# masterboard_b13.net
KiCad netlist of a schematic drawn in EAGLE
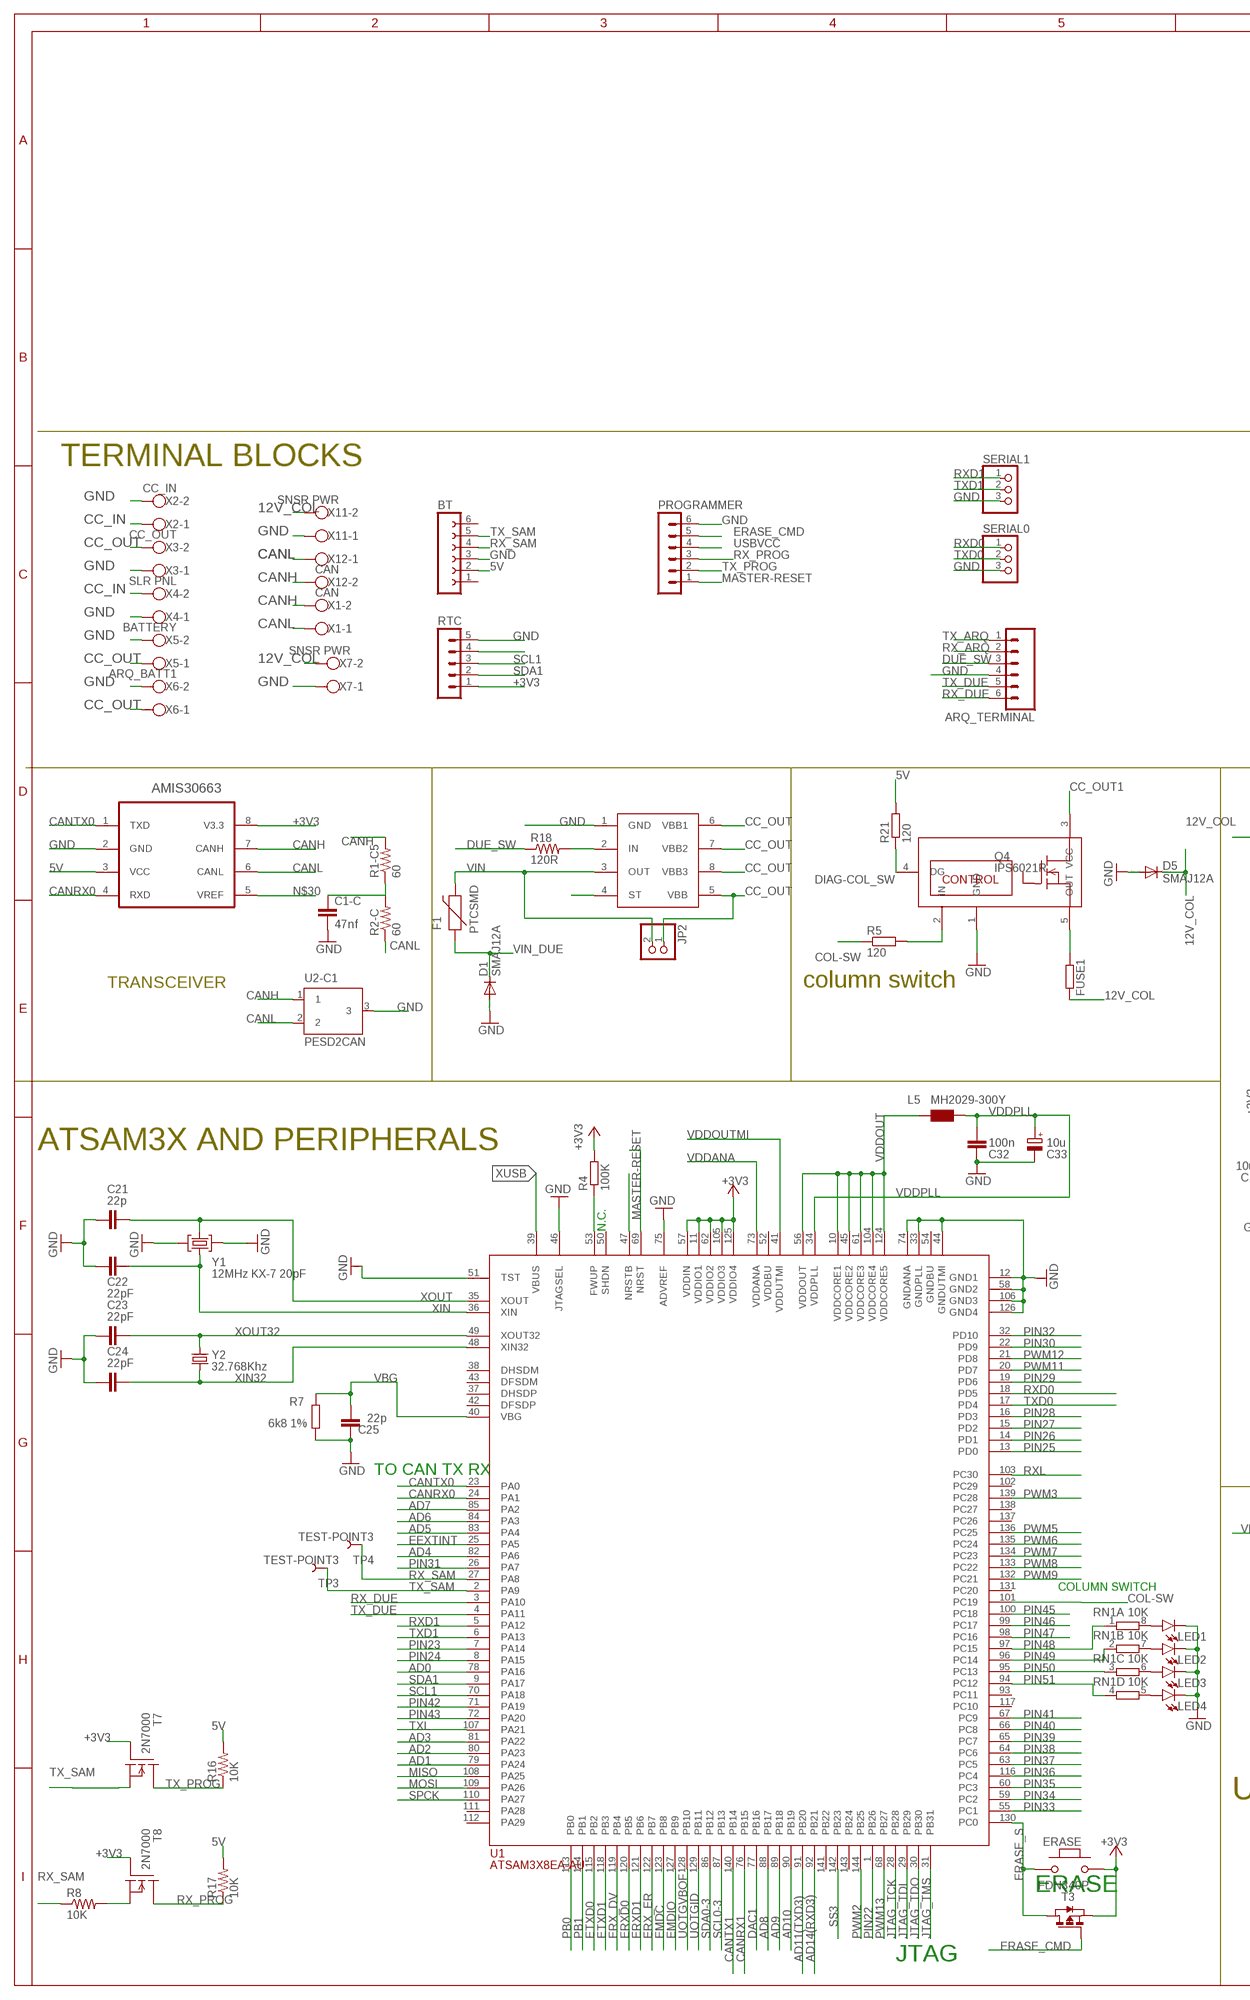
[diagram p0: schematic, sheet 1, part 1 of 2]
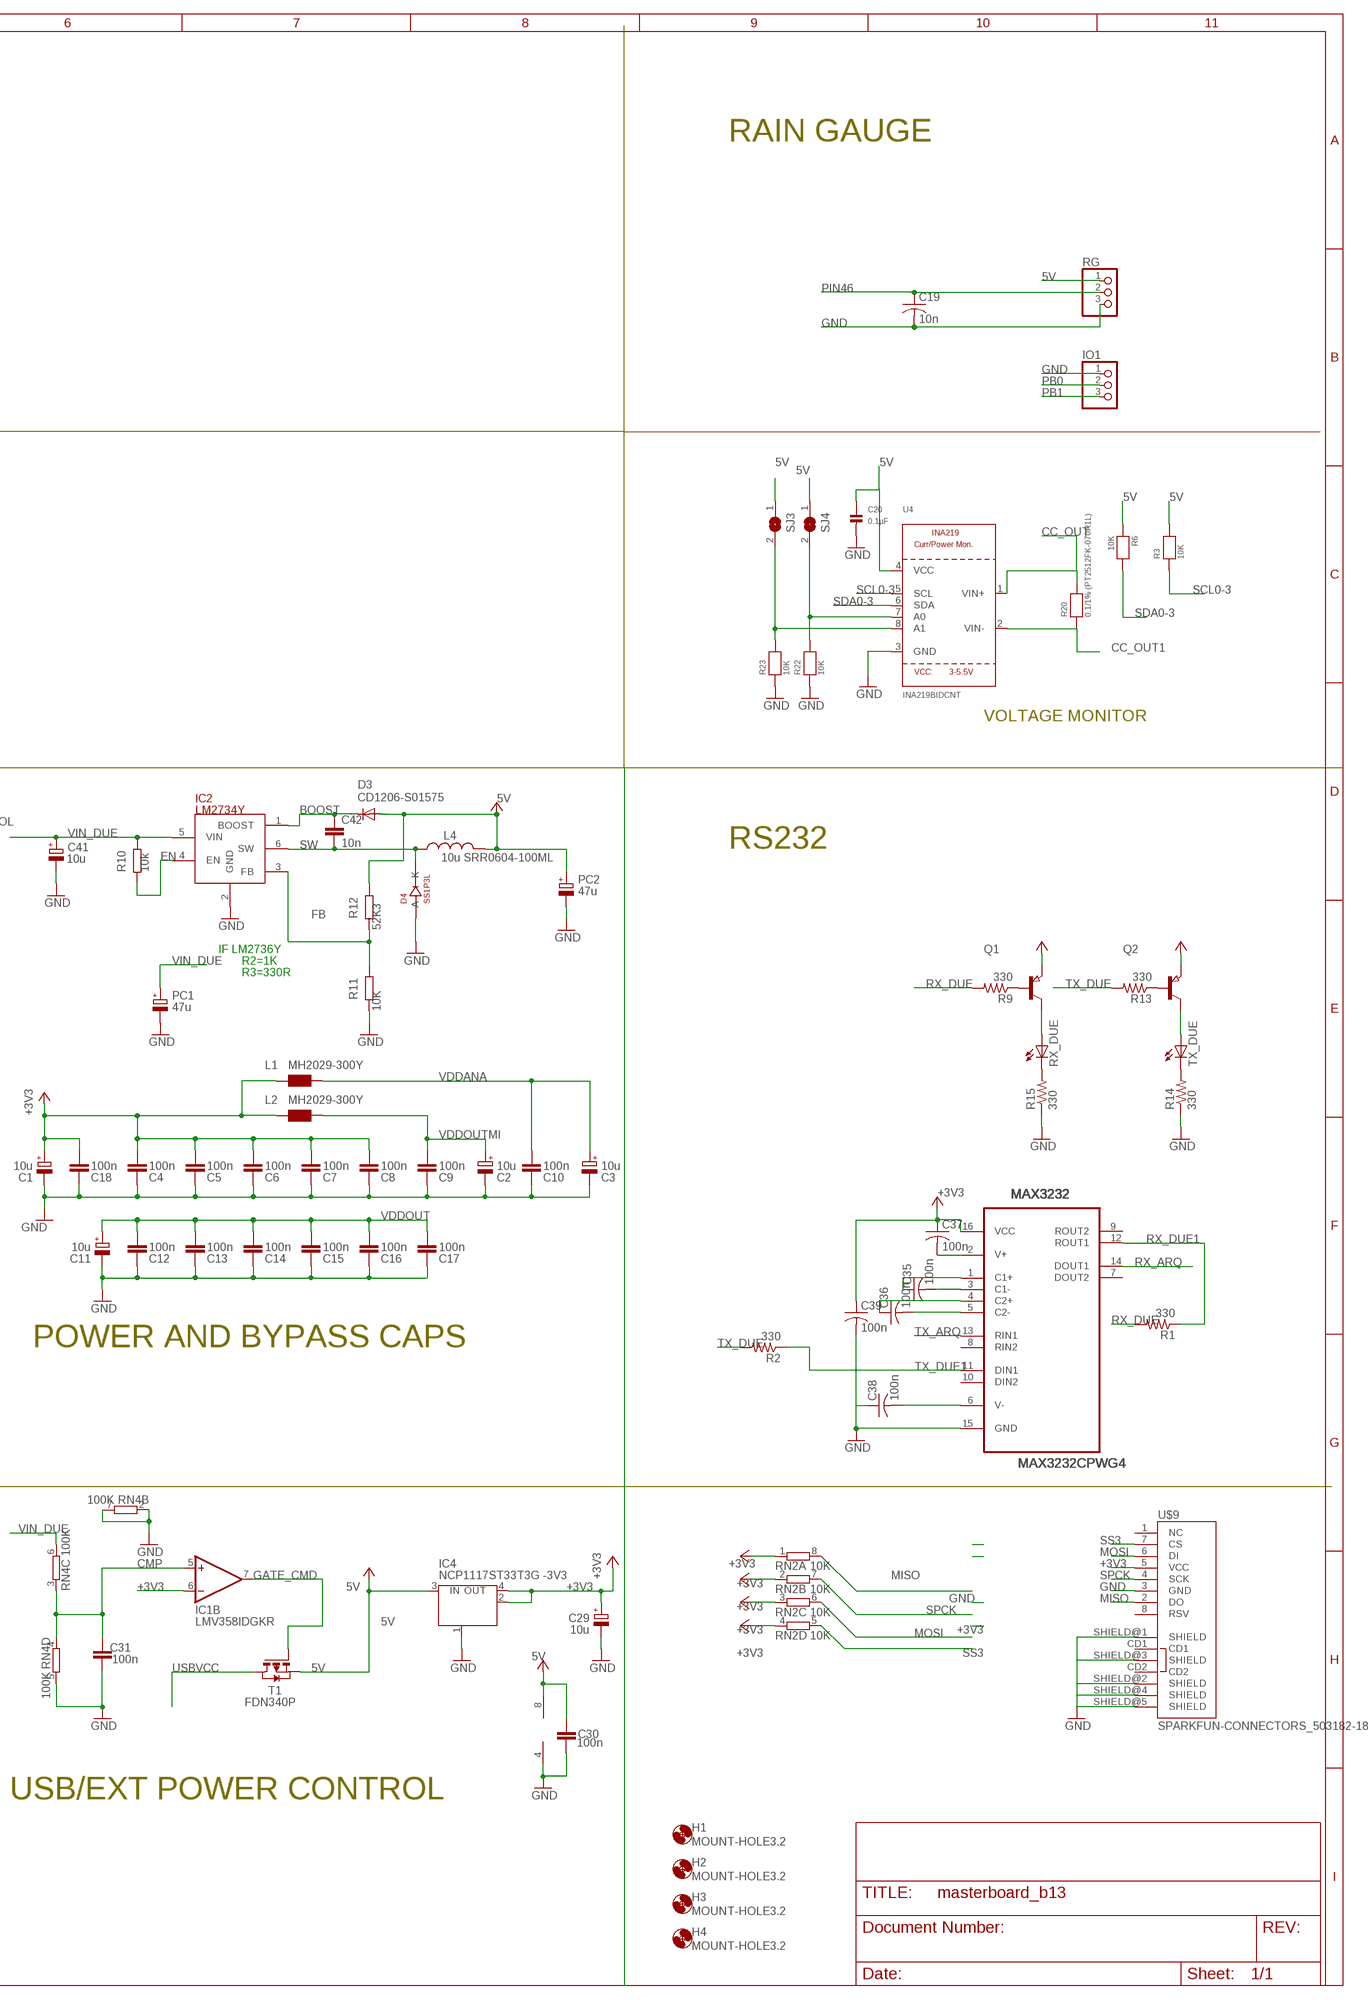
[diagram p1: schematic, sheet 1, part 2 of 2]

(export (version "E")
  (design (tool "Eeschema 10.0.6"))
  (components
    (comp (ref "ARQ_TERMINAL")
      (value "M06POLAR")
      (footprint "eagle-import:MOLEX-1X6")
      (libsource (lib "eagle-import") (part "M06POLAR"))
    )
    (comp (ref "BT")
      (value "FE06-1")
      (footprint "eagle-import:FE06")
      (libsource (lib "eagle-import") (part "FE06-1"))
    )
    (comp (ref "C1")
      (value "10u")
      (footprint "eagle-import:SMC_B")
      (libsource (lib "eagle-import") (part "CPOL-EUSMCB"))
    )
    (comp (ref "C1-C")
      (value "47nf")
      (footprint "eagle-import:C0805")
      (libsource (lib "eagle-import") (part "rcl_334_C-EUC0805"))
    )
    (comp (ref "C2")
      (value "10u")
      (footprint "eagle-import:SMC_B")
      (libsource (lib "eagle-import") (part "CPOL-EUSMCB"))
    )
    (comp (ref "C3")
      (value "10u")
      (footprint "eagle-import:SMC_B")
      (libsource (lib "eagle-import") (part "CPOL-EUSMCB"))
    )
    (comp (ref "C4")
      (value "100n")
      (footprint "eagle-import:C0402")
      (libsource (lib "eagle-import") (part "C-EUC0402"))
    )
    (comp (ref "C5")
      (value "100n")
      (footprint "eagle-import:C0402")
      (libsource (lib "eagle-import") (part "C-EUC0402"))
    )
    (comp (ref "C6")
      (value "100n")
      (footprint "eagle-import:C0402")
      (libsource (lib "eagle-import") (part "C-EUC0402"))
    )
    (comp (ref "C7")
      (value "100n")
      (footprint "eagle-import:C0402")
      (libsource (lib "eagle-import") (part "C-EUC0402"))
    )
    (comp (ref "C8")
      (value "100n")
      (footprint "eagle-import:C0402")
      (libsource (lib "eagle-import") (part "C-EUC0402"))
    )
    (comp (ref "C9")
      (value "100n")
      (footprint "eagle-import:C0402")
      (libsource (lib "eagle-import") (part "C-EUC0402"))
    )
    (comp (ref "C10")
      (value "100n")
      (footprint "eagle-import:C0402")
      (libsource (lib "eagle-import") (part "C-EUC0402"))
    )
    (comp (ref "C11")
      (value "10u")
      (footprint "eagle-import:SMC_B")
      (libsource (lib "eagle-import") (part "CPOL-EUSMCB"))
    )
    (comp (ref "C12")
      (value "100n")
      (footprint "eagle-import:C0402")
      (libsource (lib "eagle-import") (part "C-EUC0402"))
    )
    (comp (ref "C13")
      (value "100n")
      (footprint "eagle-import:C0402")
      (libsource (lib "eagle-import") (part "C-EUC0402"))
    )
    (comp (ref "C14")
      (value "100n")
      (footprint "eagle-import:C0402")
      (libsource (lib "eagle-import") (part "C-EUC0402"))
    )
    (comp (ref "C15")
      (value "100n")
      (footprint "eagle-import:C0402")
      (libsource (lib "eagle-import") (part "C-EUC0402"))
    )
    (comp (ref "C16")
      (value "100n")
      (footprint "eagle-import:C0402")
      (libsource (lib "eagle-import") (part "C-EUC0402"))
    )
    (comp (ref "C17")
      (value "100n")
      (footprint "eagle-import:C0402")
      (libsource (lib "eagle-import") (part "C-EUC0402"))
    )
    (comp (ref "C18")
      (value "100n")
      (footprint "eagle-import:C0402")
      (libsource (lib "eagle-import") (part "C-EUC0402"))
    )
    (comp (ref "C19")
      (value "10n")
      (footprint "eagle-import:C0603")
      (libsource (lib "eagle-import") (part "C-USC0603"))
    )
    (comp (ref "C20")
      (value "0.1µF")
      (footprint "eagle-import:0603-MINI")
      (fields (field (name "MPN") "04023C104KAT2A"))
      (libsource (lib "eagle-import") (part "CAP_CERAMIC0603MINI"))
    )
    (comp (ref "C21")
      (value "22p")
      (footprint "eagle-import:C0402")
      (libsource (lib "eagle-import") (part "C-EUC0402"))
    )
    (comp (ref "C22")
      (value "22pF")
      (footprint "eagle-import:C0402")
      (libsource (lib "eagle-import") (part "C-EUC0402"))
    )
    (comp (ref "C23")
      (value "22pF")
      (footprint "eagle-import:C0402")
      (libsource (lib "eagle-import") (part "C-EUC0402"))
    )
    (comp (ref "C24")
      (value "22pF")
      (footprint "eagle-import:C0402")
      (libsource (lib "eagle-import") (part "C-EUC0402"))
    )
    (comp (ref "C25")
      (value "22p")
      (footprint "eagle-import:C0402")
      (libsource (lib "eagle-import") (part "C-EUC0402"))
    )
    (comp (ref "C29")
      (value "10u")
      (footprint "eagle-import:SMC_B")
      (libsource (lib "eagle-import") (part "CPOL-EUSMCB"))
    )
    (comp (ref "C30")
      (value "100n")
      (footprint "eagle-import:C0402")
      (libsource (lib "eagle-import") (part "C-EUC0402"))
    )
    (comp (ref "C31")
      (value "100n")
      (footprint "eagle-import:C0402")
      (libsource (lib "eagle-import") (part "C-EUC0402"))
    )
    (comp (ref "C32")
      (value "100n")
      (footprint "eagle-import:C0402")
      (libsource (lib "eagle-import") (part "C-EUC0402"))
    )
    (comp (ref "C33")
      (value "10u")
      (footprint "eagle-import:SMC_B")
      (libsource (lib "eagle-import") (part "CPOL-EUSMCB"))
    )
    (comp (ref "C35")
      (value "100n")
      (footprint "eagle-import:C0603")
      (libsource (lib "eagle-import") (part "C-USC0603"))
    )
    (comp (ref "C36")
      (value "100n")
      (footprint "eagle-import:C0603")
      (libsource (lib "eagle-import") (part "C-USC0603"))
    )
    (comp (ref "C37")
      (value "100n")
      (footprint "eagle-import:C0603")
      (libsource (lib "eagle-import") (part "C-USC0603"))
    )
    (comp (ref "C38")
      (value "100n")
      (footprint "eagle-import:C0603")
      (libsource (lib "eagle-import") (part "C-USC0603"))
    )
    (comp (ref "C39")
      (value "100n")
      (footprint "eagle-import:C0603")
      (libsource (lib "eagle-import") (part "C-USC0603"))
    )
    (comp (ref "C41")
      (value "10u")
      (footprint "eagle-import:SMC_B")
      (libsource (lib "eagle-import") (part "CPOL-EUSMCB"))
    )
    (comp (ref "C42")
      (value "10n")
      (footprint "eagle-import:C0603-ROUND")
      (libsource (lib "eagle-import") (part "C-EUC0603"))
    )
    (comp (ref "D1")
      (value "SMAJ12A")
      (footprint "eagle-import:DO214AC")
      (libsource (lib "eagle-import") (part "DIODE-DO214AC"))
    )
    (comp (ref "D3")
      (value "CD1206-S01575")
      (footprint "eagle-import:MINIMELF")
      (libsource (lib "eagle-import") (part "DIODE-MINIMELF"))
    )
    (comp (ref "D4")
      (value "SS1P3L")
      (footprint "eagle-import:DO220AAL")
      (libsource (lib "eagle-import") (part "SS1P3L"))
    )
    (comp (ref "D5")
      (value "SMAJ12A")
      (footprint "eagle-import:DO214AC")
      (libsource (lib "eagle-import") (part "DIODE-DO214AC"))
    )
    (comp (ref "ERASE")
      (value "MYSMD_PB157")
      (footprint "eagle-import:SMD_157SW")
      (libsource (lib "eagle-import") (part "MYSMD_PB157"))
    )
    (comp (ref "F1")
      (value "PTCSMD")
      (footprint "eagle-import:PTC-1206")
      (libsource (lib "eagle-import") (part "PTCSMD"))
    )
    (comp (ref "FUSE1")
      (value "R-EU_1812X7R")
      (footprint "eagle-import:1812X7R")
      (libsource (lib "eagle-import") (part "R-EU_1812X7R"))
    )
    (comp (ref "H1")
      (value "MOUNT-HOLE3.2")
      (footprint "eagle-import:3,2")
      (libsource (lib "eagle-import") (part "MOUNT-HOLE3.2"))
    )
    (comp (ref "H2")
      (value "MOUNT-HOLE3.2")
      (footprint "eagle-import:3,2")
      (libsource (lib "eagle-import") (part "MOUNT-HOLE3.2"))
    )
    (comp (ref "H3")
      (value "MOUNT-HOLE3.2")
      (footprint "eagle-import:3,2")
      (libsource (lib "eagle-import") (part "MOUNT-HOLE3.2"))
    )
    (comp (ref "H4")
      (value "MOUNT-HOLE3.2")
      (footprint "eagle-import:3,2")
      (libsource (lib "eagle-import") (part "MOUNT-HOLE3.2"))
    )
    (comp (ref "IC1")
      (value "LMV358IDGKR")
      (footprint "eagle-import:MSOP08")
      (libsource (lib "eagle-import") (part "LMV358?MMX"))
    )
    (comp (ref "IC2")
      (value "LM2734Y")
      (footprint "eagle-import:SOT23-6")
      (libsource (lib "eagle-import") (part "LM2736Y"))
    )
    (comp (ref "IC4")
      (value "NCP1117ST33T3G -3V3")
      (footprint "eagle-import:SOT223")
      (libsource (lib "eagle-import") (part "MC33269ST-3.3T3"))
    )
    (comp (ref "IO1")
      (value "PINHD-1X3")
      (footprint "eagle-import:1X03")
      (libsource (lib "eagle-import") (part "PINHD-1X3"))
    )
    (comp (ref "JP2")
      (value "PINHD-1X2")
      (footprint "eagle-import:1X02")
      (libsource (lib "eagle-import") (part "PINHD-1X2"))
    )
    (comp (ref "L1")
      (value "MH2029-300Y")
      (footprint "eagle-import:0805")
      (libsource (lib "eagle-import") (part "WE-CBF_0805"))
    )
    (comp (ref "L2")
      (value "MH2029-300Y")
      (footprint "eagle-import:0805")
      (libsource (lib "eagle-import") (part "WE-CBF_0805"))
    )
    (comp (ref "L4")
      (value "10u SRR0604-100ML")
      (footprint "eagle-import:SRR0604")
      (libsource (lib "eagle-import") (part "L-USSRR0604"))
    )
    (comp (ref "L5")
      (value "MH2029-300Y")
      (footprint "eagle-import:0805")
      (libsource (lib "eagle-import") (part "WE-CBF_0805"))
    )
    (comp (ref "LED1")
      (value "LED0603")
      (footprint "eagle-import:LED-0603")
      (libsource (lib "eagle-import") (part "LED0603"))
    )
    (comp (ref "LED2")
      (value "LED0603")
      (footprint "eagle-import:LED-0603")
      (libsource (lib "eagle-import") (part "LED0603"))
    )
    (comp (ref "LED3")
      (value "LED0603")
      (footprint "eagle-import:LED-0603")
      (libsource (lib "eagle-import") (part "LED0603"))
    )
    (comp (ref "LED4")
      (value "LED0603")
      (footprint "eagle-import:LED-0603")
      (libsource (lib "eagle-import") (part "LED0603"))
    )
    (comp (ref "MAX3232")
      (value "MAX3232CPWG4")
      (footprint "eagle-import:SOP65P640X120-16N")
      (libsource (lib "eagle-import") (part "MAX3232CPWG4"))
    )
    (comp (ref "PC1")
      (value "47u")
      (footprint "eagle-import:PANASONIC_D")
      (libsource (lib "eagle-import") (part "CPOL-EUD"))
    )
    (comp (ref "PC2")
      (value "47u")
      (footprint "eagle-import:PANASONIC_D")
      (libsource (lib "eagle-import") (part "CPOL-EUD"))
    )
    (comp (ref "PROGRAMMER")
      (value "MA06-1")
      (footprint "eagle-import:MA06-1")
      (libsource (lib "eagle-import") (part "MA06-1"))
    )
    (comp (ref "Q1")
      (value "PNP-TRANSISTOR_SOT23")
      (footprint "eagle-import:SOT23")
      (libsource (lib "eagle-import") (part "PNP-TRANSISTOR_SOT23"))
    )
    (comp (ref "Q2")
      (value "PNP-TRANSISTOR_SOT23")
      (footprint "eagle-import:SOT23")
      (libsource (lib "eagle-import") (part "PNP-TRANSISTOR_SOT23"))
    )
    (comp (ref "Q4")
      (value "IPS6021R")
      (footprint "eagle-import:DPAK-5LEAD")
      (libsource (lib "eagle-import") (part "IPS6021R"))
    )
    (comp (ref "R1")
      (value "330")
      (footprint "eagle-import:R0603")
      (libsource (lib "eagle-import") (part "R-US_R0603"))
    )
    (comp (ref "R1-C5")
      (value "60")
      (footprint "eagle-import:R2512")
      (libsource (lib "eagle-import") (part "rcl_334_R-US_R2512"))
    )
    (comp (ref "R2")
      (value "330")
      (footprint "eagle-import:R0603")
      (libsource (lib "eagle-import") (part "R-US_R0603"))
    )
    (comp (ref "R2-C")
      (value "60")
      (footprint "eagle-import:R2512")
      (libsource (lib "eagle-import") (part "rcl_334_R-US_R2512"))
    )
    (comp (ref "R3")
      (value "10K")
      (footprint "eagle-import:0603-MINI")
      (fields (field (name "MPN") "TNPW040210K0BEED"))
      (libsource (lib "eagle-import") (part "RESISTOR0603MINI"))
    )
    (comp (ref "R4")
      (value "100K")
      (footprint "eagle-import:R0402")
      (libsource (lib "eagle-import") (part "R-EU_R0402"))
    )
    (comp (ref "R5")
      (value "120")
      (footprint "eagle-import:R0603")
      (libsource (lib "eagle-import") (part "rcl_334_R-EU_R0603"))
    )
    (comp (ref "R6")
      (value "10K")
      (footprint "eagle-import:0603-MINI")
      (fields (field (name "MPN") "TNPW040210K0BEED"))
      (libsource (lib "eagle-import") (part "RESISTOR0603MINI"))
    )
    (comp (ref "R7")
      (value "6k8 1%")
      (footprint "eagle-import:R0603-ROUND")
      (libsource (lib "eagle-import") (part "R-EU_R0603"))
    )
    (comp (ref "R8")
      (value "10K")
      (footprint "eagle-import:R0603")
      (libsource (lib "eagle-import") (part "rcl_334_R-US_R0603"))
    )
    (comp (ref "R9")
      (value "330")
      (footprint "eagle-import:R0603")
      (libsource (lib "eagle-import") (part "R-US_R0603"))
    )
    (comp (ref "R10")
      (value "10k")
      (footprint "eagle-import:R0402")
      (libsource (lib "eagle-import") (part "R-EU_R0402"))
    )
    (comp (ref "R11")
      (value "10K")
      (footprint "eagle-import:R0603-ROUND")
      (libsource (lib "eagle-import") (part "R-EU_0603-RND"))
    )
    (comp (ref "R12")
      (value "52K3")
      (footprint "eagle-import:R0603-ROUND")
      (libsource (lib "eagle-import") (part "R-EU_0603-RND"))
    )
    (comp (ref "R13")
      (value "330")
      (footprint "eagle-import:R0603")
      (libsource (lib "eagle-import") (part "R-US_R0603"))
    )
    (comp (ref "R14")
      (value "330")
      (footprint "eagle-import:R0603")
      (libsource (lib "eagle-import") (part "R-US_R0603"))
    )
    (comp (ref "R15")
      (value "330")
      (footprint "eagle-import:R0603")
      (libsource (lib "eagle-import") (part "R-US_R0603"))
    )
    (comp (ref "R16")
      (value "10K")
      (footprint "eagle-import:R0603")
      (libsource (lib "eagle-import") (part "rcl_334_R-US_R0603"))
    )
    (comp (ref "R17")
      (value "10K")
      (footprint "eagle-import:R0603")
      (libsource (lib "eagle-import") (part "rcl_334_R-US_R0603"))
    )
    (comp (ref "R18")
      (value "120R")
      (footprint "eagle-import:R0603")
      (libsource (lib "eagle-import") (part "rcl_334_R-US_R0603"))
    )
    (comp (ref "R20")
      (value "0.1/1% (PT2512FK-070R1L)")
      (footprint "eagle-import:2512")
      (libsource (lib "eagle-import") (part "RESISTOR2512"))
    )
    (comp (ref "R21")
      (value "120")
      (footprint "eagle-import:R0603")
      (libsource (lib "eagle-import") (part "rcl_334_R-EU_R0603"))
    )
    (comp (ref "R22")
      (value "10K")
      (footprint "eagle-import:0603-MINI")
      (fields (field (name "MPN") "TNPW040210K0BEED"))
      (libsource (lib "eagle-import") (part "RESISTOR0603MINI"))
    )
    (comp (ref "R23")
      (value "10K")
      (footprint "eagle-import:0603-MINI")
      (fields (field (name "MPN") "TNPW040210K0BEED"))
      (libsource (lib "eagle-import") (part "RESISTOR0603MINI"))
    )
    (comp (ref "RG")
      (value "PINHD-1X3")
      (footprint "eagle-import:1X03")
      (libsource (lib "eagle-import") (part "PINHD-1X3"))
    )
    (comp (ref "RN1")
      (value "10K")
      (footprint "eagle-import:CAT16")
      (libsource (lib "eagle-import") (part "4R-NCAT16"))
    )
    (comp (ref "RN2")
      (value "10K")
      (footprint "eagle-import:CAT16")
      (libsource (lib "eagle-import") (part "4R-NCAT16"))
    )
    (comp (ref "RN4")
      (value "100K")
      (footprint "eagle-import:CAT16")
      (libsource (lib "eagle-import") (part "4R-NCAT16"))
    )
    (comp (ref "RTC")
      (value "MA05-1")
      (footprint "eagle-import:MA05-1")
      (libsource (lib "eagle-import") (part "MA05-1"))
    )
    (comp (ref "RX_DUE")
      (value "LEDCHIPLED_0603")
      (footprint "eagle-import:CHIPLED_0603")
      (libsource (lib "eagle-import") (part "LEDCHIPLED_0603"))
    )
    (comp (ref "SERIAL0")
      (value "PINHD-1X3")
      (footprint "eagle-import:1X03")
      (libsource (lib "eagle-import") (part "PINHD-1X3"))
    )
    (comp (ref "SERIAL1")
      (value "PINHD-1X3")
      (footprint "eagle-import:1X03")
      (libsource (lib "eagle-import") (part "PINHD-1X3"))
    )
    (comp (ref "SJ3")
      (value "SOLDERJUMPERREFLOW_NOPASTE")
      (footprint "eagle-import:SOLDERJUMPER_REFLOW_NOPASTE")
      (libsource (lib "eagle-import") (part "SOLDERJUMPERREFLOW_NOPASTE"))
    )
    (comp (ref "SJ4")
      (value "SOLDERJUMPERREFLOW_NOPASTE")
      (footprint "eagle-import:SOLDERJUMPER_REFLOW_NOPASTE")
      (libsource (lib "eagle-import") (part "SOLDERJUMPERREFLOW_NOPASTE"))
    )
    (comp (ref "T1")
      (value "FDN340P")
      (footprint "eagle-import:SOT-23")
      (libsource (lib "eagle-import") (part "PMOSSOT23"))
    )
    (comp (ref "T3")
      (value "FDN340P")
      (footprint "eagle-import:SOT-23")
      (libsource (lib "eagle-import") (part "PMOSSOT23"))
    )
    (comp (ref "T7")
      (value "2N7000")
      (footprint "eagle-import:SOT23")
      (libsource (lib "eagle-import") (part "2N7000"))
    )
    (comp (ref "T8")
      (value "2N7000")
      (footprint "eagle-import:SOT23")
      (libsource (lib "eagle-import") (part "2N7000"))
    )
    (comp (ref "TP3")
      (value "TEST-POINT3")
      (footprint "eagle-import:PAD.03X.03")
      (libsource (lib "eagle-import") (part "TEST-POINT3"))
    )
    (comp (ref "TP4")
      (value "TEST-POINT3")
      (footprint "eagle-import:PAD.03X.03")
      (libsource (lib "eagle-import") (part "TEST-POINT3"))
    )
    (comp (ref "TX_DUE")
      (value "LEDCHIPLED_0603")
      (footprint "eagle-import:CHIPLED_0603")
      (libsource (lib "eagle-import") (part "LEDCHIPLED_0603"))
    )
    (comp (ref "U$9")
      (value "SPARKFUN-CONNECTORS_503182-1853")
      (footprint "eagle-import:SPARKFUN-CONNECTORS_503182-1853")
      (libsource (lib "eagle-import") (part "SPARKFUN-CONNECTORS_503182-1853"))
    )
    (comp (ref "U1")
      (value "ATSAM3X8EA-AU")
      (footprint "eagle-import:LQFP144")
      (libsource (lib "eagle-import") (part "ATSAM3X/AAU"))
    )
    (comp (ref "U2")
      (value "INF-PG-DSO-8-24_L_1")
      (footprint "eagle-import:INF-PG-DSO-8-24_L_1PRIMARY")
      (libsource (lib "eagle-import") (part "INF-PG-DSO-8-24_L_1"))
    )
    (comp (ref "U2-C")
      (value "AMIS30663CAN")
      (footprint "eagle-import:SOIC8")
      (fields (field (name "MPN") "AMIS30663"))
      (libsource (lib "eagle-import") (part "AMIS30663CAN"))
    )
    (comp (ref "U2-C1")
      (value "PESD2CAN")
      (footprint "eagle-import:SOT23")
      (libsource (lib "eagle-import") (part "PESD2CAN"))
    )
    (comp (ref "U4")
      (value "INA219BIDCNT")
      (footprint "eagle-import:SOT23-8")
      (libsource (lib "eagle-import") (part "INA219"))
    )
    (comp (ref "X1")
      (value "CAN")
      (footprint "eagle-import:W237-102")
      (fields (field (name "MPN") "237-102"))
      (libsource (lib "eagle-import") (part "W237-102"))
    )
    (comp (ref "X2")
      (value "CC_IN")
      (footprint "eagle-import:W237-102")
      (fields (field (name "MPN") "237-102"))
      (libsource (lib "eagle-import") (part "W237-102"))
    )
    (comp (ref "X3")
      (value "CC_OUT")
      (footprint "eagle-import:W237-102")
      (fields (field (name "MPN") "237-102"))
      (libsource (lib "eagle-import") (part "W237-102"))
    )
    (comp (ref "X4")
      (value "SLR PNL")
      (footprint "eagle-import:W237-102")
      (fields (field (name "MPN") "237-102"))
      (libsource (lib "eagle-import") (part "W237-102"))
    )
    (comp (ref "X5")
      (value "BATTERY")
      (footprint "eagle-import:W237-102")
      (fields (field (name "MPN") "237-102"))
      (libsource (lib "eagle-import") (part "W237-102"))
    )
    (comp (ref "X6")
      (value "ARQ_BATT1")
      (footprint "eagle-import:W237-102")
      (fields (field (name "MPN") "237-102"))
      (libsource (lib "eagle-import") (part "W237-102"))
    )
    (comp (ref "X7")
      (value "SNSR PWR")
      (footprint "eagle-import:W237-102")
      (fields (field (name "MPN") "237-102"))
      (libsource (lib "eagle-import") (part "W237-102"))
    )
    (comp (ref "X11")
      (value "SNSR PWR")
      (footprint "eagle-import:W237-102")
      (fields (field (name "MPN") "237-102"))
      (libsource (lib "eagle-import") (part "W237-102"))
    )
    (comp (ref "X12")
      (value "CAN")
      (footprint "eagle-import:W237-102")
      (fields (field (name "MPN") "237-102"))
      (libsource (lib "eagle-import") (part "W237-102"))
    )
    (comp (ref "Y1")
      (value "12MHz KX-7 20pF")
      (footprint "eagle-import:CRYSTAL-3.2-2.5")
      (libsource (lib "eagle-import") (part "CRYSTAL-3.2-2.5"))
    )
    (comp (ref "Y2")
      (value "32.768Khz")
      (footprint "eagle-import:RESONATOR_EPSON_FC_145")
      (libsource (lib "eagle-import") (part "RESONATOR_EPSON_FC_145"))
    )
  )
  (nets
    (net (code "1") (name "+3V3") (class "Default")
      (node (ref "C1") (pin "+") (pinfunction "+_+") (pintype "passive"))
      (node (ref "C18") (pin "2") (pinfunction "2_2") (pintype "passive"))
      (node (ref "C29") (pin "+") (pinfunction "+_+") (pintype "passive"))
      (node (ref "C37") (pin "1") (pinfunction "1_1") (pintype "passive"))
      (node (ref "C39") (pin "1") (pinfunction "1_1") (pintype "passive"))
      (node (ref "C4") (pin "2") (pinfunction "2_2") (pintype "passive"))
      (node (ref "C5") (pin "2") (pinfunction "2_2") (pintype "passive"))
      (node (ref "C6") (pin "2") (pinfunction "2_2") (pintype "passive"))
      (node (ref "C7") (pin "2") (pinfunction "2_2") (pintype "passive"))
      (node (ref "C8") (pin "2") (pinfunction "2_2") (pintype "passive"))
      (node (ref "ERASE") (pin "1") (pinfunction "1_1") (pintype "passive"))
      (node (ref "IC1") (pin "6") (pinfunction "-IN_6") (pintype "input"))
      (node (ref "IC4") (pin "2") (pinfunction "OUT_2") (pintype "passive"))
      (node (ref "IC4") (pin "4") (pinfunction "OUT_4") (pintype "passive"))
      (node (ref "L1") (pin "1") (pinfunction "1_1") (pintype "passive"))
      (node (ref "L2") (pin "1") (pinfunction "1_1") (pintype "passive"))
      (node (ref "MAX3232") (pin "16") (pinfunction "VCC_16") (pintype "power_in"))
      (node (ref "Q1") (pin "2") (pinfunction "E_2") (pintype "passive"))
      (node (ref "Q2") (pin "2") (pinfunction "E_2") (pintype "passive"))
      (node (ref "R4") (pin "2") (pinfunction "2_2") (pintype "passive"))
      (node (ref "RN2") (pin "1") (pinfunction "1_1") (pintype "passive"))
      (node (ref "RN2") (pin "2") (pinfunction "1_2") (pintype "passive"))
      (node (ref "RN2") (pin "3") (pinfunction "1_3") (pintype "passive"))
      (node (ref "RN2") (pin "4") (pinfunction "1_4") (pintype "passive"))
      (node (ref "RTC") (pin "1") (pinfunction "1_1") (pintype "passive"))
      (node (ref "T3") (pin "2") (pinfunction "S_2") (pintype "passive"))
      (node (ref "T7") (pin "1") (pinfunction "G_1") (pintype "passive"))
      (node (ref "T8") (pin "1") (pinfunction "G_1") (pintype "passive"))
      (node (ref "U$9") (pin "5") (pinfunction "VCC_5") (pintype "bidirectional"))
      (node (ref "U1") (pin "105") (pinfunction "VDDIO3_105") (pintype "power_in"))
      (node (ref "U1") (pin "11") (pinfunction "VDDIO1_11") (pintype "power_in"))
      (node (ref "U1") (pin "125") (pinfunction "VDDIO4_125") (pintype "power_in"))
      (node (ref "U1") (pin "57") (pinfunction "VDDIN_57") (pintype "power_in"))
      (node (ref "U1") (pin "62") (pinfunction "VDDIO2_62") (pintype "power_in"))
      (node (ref "U2-C") (pin "8") (pinfunction "V3.3_8") (pintype "bidirectional"))
    )
    (net (code "2") (name "+5V") (class "Default")
      (node (ref "BT") (pin "2") (pinfunction "2_2") (pintype "passive"))
      (node (ref "C20") (pin "1") (pinfunction "P$1_1") (pintype "passive"))
      (node (ref "C30") (pin "2") (pinfunction "2_2") (pintype "passive"))
      (node (ref "D3") (pin "A") (pinfunction "A_A") (pintype "passive"))
      (node (ref "IC1") (pin "8") (pinfunction "V+_8") (pintype "power_in"))
      (node (ref "IC4") (pin "3") (pinfunction "IN_3") (pintype "input"))
      (node (ref "L4") (pin "P$2") (pinfunction "2_P$2") (pintype "passive"))
      (node (ref "PC2") (pin "+") (pinfunction "+_+") (pintype "passive"))
      (node (ref "R12") (pin "1") (pinfunction "1_1") (pintype "passive"))
      (node (ref "R16") (pin "2") (pinfunction "2_2") (pintype "passive"))
      (node (ref "R17") (pin "2") (pinfunction "2_2") (pintype "passive"))
      (node (ref "R21") (pin "2") (pinfunction "2_2") (pintype "passive"))
      (node (ref "R3") (pin "2") (pinfunction "2_2") (pintype "passive"))
      (node (ref "R6") (pin "1") (pinfunction "1_1") (pintype "passive"))
      (node (ref "RG") (pin "1") (pinfunction "1_1") (pintype "passive"))
      (node (ref "SJ3") (pin "1") (pinfunction "1_1") (pintype "passive"))
      (node (ref "SJ4") (pin "1") (pinfunction "1_1") (pintype "passive"))
      (node (ref "T1") (pin "2") (pinfunction "S_2") (pintype "passive"))
      (node (ref "U2-C") (pin "3") (pinfunction "VCC_3") (pintype "bidirectional"))
      (node (ref "U4") (pin "4") (pinfunction "VCC_4") (pintype "bidirectional"))
    )
    (net (code "3") (name "/12V_COL") (class "Default")
      (node (ref "D5") (pin "C") (pinfunction "C_C") (pintype "passive"))
      (node (ref "FUSE1") (pin "2") (pinfunction "2_2") (pintype "passive"))
      (node (ref "X11") (pin "2") (pinfunction "KL_2") (pintype "passive"))
      (node (ref "X7") (pin "2") (pinfunction "KL_2") (pintype "passive"))
    )
    (net (code "4") (name "/AD0") (class "Default")
      (node (ref "U1") (pin "78") (pinfunction "PA16_78") (pintype "bidirectional"))
    )
    (net (code "5") (name "/AD1") (class "Default")
      (node (ref "U1") (pin "79") (pinfunction "PA24_79") (pintype "bidirectional"))
    )
    (net (code "6") (name "/AD2") (class "Default")
      (node (ref "U1") (pin "80") (pinfunction "PA23_80") (pintype "bidirectional"))
    )
    (net (code "7") (name "/AD3") (class "Default")
      (node (ref "U1") (pin "81") (pinfunction "PA22_81") (pintype "bidirectional"))
    )
    (net (code "8") (name "/AD4") (class "Default")
      (node (ref "U1") (pin "82") (pinfunction "PA6_82") (pintype "bidirectional"))
    )
    (net (code "9") (name "/AD5") (class "Default")
      (node (ref "U1") (pin "83") (pinfunction "PA4_83") (pintype "bidirectional"))
    )
    (net (code "10") (name "/AD6") (class "Default")
      (node (ref "U1") (pin "84") (pinfunction "PA3_84") (pintype "bidirectional"))
    )
    (net (code "11") (name "/AD7") (class "Default")
      (node (ref "U1") (pin "85") (pinfunction "PA2_85") (pintype "bidirectional"))
    )
    (net (code "12") (name "/AD8") (class "Default")
      (node (ref "U1") (pin "88") (pinfunction "PB17_88") (pintype "bidirectional"))
    )
    (net (code "13") (name "/AD9") (class "Default")
      (node (ref "U1") (pin "89") (pinfunction "PB18_89") (pintype "bidirectional"))
    )
    (net (code "14") (name "/AD10") (class "Default")
      (node (ref "U1") (pin "90") (pinfunction "PB19_90") (pintype "bidirectional"))
    )
    (net (code "15") (name "/AD11(TXD3)") (class "Default")
      (node (ref "U1") (pin "91") (pinfunction "PB20_91") (pintype "bidirectional"))
    )
    (net (code "16") (name "/AD14(RXD3)") (class "Default")
      (node (ref "U1") (pin "92") (pinfunction "PB21_92") (pintype "bidirectional"))
    )
    (net (code "17") (name "/BOOST") (class "Default")
      (node (ref "C42") (pin "1") (pinfunction "1_1") (pintype "passive"))
      (node (ref "D3") (pin "C") (pinfunction "C_C") (pintype "passive"))
      (node (ref "IC2") (pin "1") (pinfunction "BOOST_1") (pintype "input"))
    )
    (net (code "18") (name "/CANH") (class "Default")
      (node (ref "R1-C5") (pin "2") (pinfunction "2_2") (pintype "passive"))
      (node (ref "U2-C") (pin "7") (pinfunction "CANH_7") (pintype "bidirectional"))
      (node (ref "U2-C1") (pin "1") (pinfunction "1_1") (pintype "input"))
      (node (ref "X1") (pin "2") (pinfunction "KL_2") (pintype "passive"))
      (node (ref "X12") (pin "2") (pinfunction "KL_2") (pintype "passive"))
    )
    (net (code "19") (name "/CANL") (class "Default")
      (node (ref "R2-C") (pin "1") (pinfunction "1_1") (pintype "passive"))
      (node (ref "U2-C") (pin "6") (pinfunction "CANL_6") (pintype "bidirectional"))
      (node (ref "U2-C1") (pin "2") (pinfunction "2_2") (pintype "power_in"))
      (node (ref "X1") (pin "1") (pinfunction "KL_1") (pintype "passive"))
      (node (ref "X12") (pin "1") (pinfunction "KL_1") (pintype "passive"))
    )
    (net (code "20") (name "/CANRX0") (class "Default")
      (node (ref "U1") (pin "24") (pinfunction "PA1_24") (pintype "bidirectional"))
      (node (ref "U2-C") (pin "4") (pinfunction "RXD_4") (pintype "bidirectional"))
    )
    (net (code "21") (name "/CANRX1") (class "Default")
      (node (ref "U1") (pin "76") (pinfunction "PB15_76") (pintype "bidirectional"))
    )
    (net (code "22") (name "/CANTX0") (class "Default")
      (node (ref "U1") (pin "23") (pinfunction "PA0_23") (pintype "bidirectional"))
      (node (ref "U2-C") (pin "1") (pinfunction "TXD_1") (pintype "bidirectional"))
    )
    (net (code "23") (name "/CANTX1") (class "Default")
      (node (ref "U1") (pin "140") (pinfunction "PB14_140") (pintype "bidirectional"))
    )
    (net (code "24") (name "/CC_IN") (class "Default")
      (node (ref "X2") (pin "1") (pinfunction "KL_1") (pintype "passive"))
      (node (ref "X4") (pin "2") (pinfunction "KL_2") (pintype "passive"))
    )
    (net (code "25") (name "/CC_OUT") (class "Default")
      (node (ref "JP2") (pin "1") (pinfunction "1_1") (pintype "passive"))
      (node (ref "R20") (pin "2") (pinfunction "2_2") (pintype "passive"))
      (node (ref "U2") (pin "5") (pinfunction "VBB_5") (pintype "bidirectional"))
      (node (ref "U2") (pin "6") (pinfunction "VBB1_6") (pintype "bidirectional"))
      (node (ref "U2") (pin "7") (pinfunction "VBB2_7") (pintype "bidirectional"))
      (node (ref "U2") (pin "8") (pinfunction "VBB3_8") (pintype "bidirectional"))
      (node (ref "U4") (pin "1") (pinfunction "VIN+_1") (pintype "bidirectional"))
      (node (ref "X3") (pin "2") (pinfunction "KL_2") (pintype "passive"))
      (node (ref "X5") (pin "1") (pinfunction "KL_1") (pintype "passive"))
      (node (ref "X6") (pin "1") (pinfunction "KL_1") (pintype "passive"))
    )
    (net (code "26") (name "/CC_OUT1") (class "Default")
      (node (ref "Q4") (pin "3") (pinfunction "VCC_3") (pintype "passive"))
      (node (ref "R20") (pin "1") (pinfunction "1_1") (pintype "passive"))
      (node (ref "U4") (pin "2") (pinfunction "VIN-_2") (pintype "bidirectional"))
    )
    (net (code "27") (name "/CMP") (class "Default")
      (node (ref "C31") (pin "2") (pinfunction "2_2") (pintype "passive"))
      (node (ref "IC1") (pin "5") (pinfunction "+IN_5") (pintype "input"))
      (node (ref "RN4") (pin "3") (pinfunction "1_3") (pintype "passive"))
      (node (ref "RN4") (pin "4") (pinfunction "1_4") (pintype "passive"))
    )
    (net (code "28") (name "/COL-SW") (class "Default")
      (node (ref "R5") (pin "1") (pinfunction "1_1") (pintype "passive"))
      (node (ref "U1") (pin "101") (pinfunction "PC19_101") (pintype "bidirectional"))
    )
    (net (code "29") (name "/DAC1") (class "Default")
      (node (ref "U1") (pin "77") (pinfunction "PB16_77") (pintype "bidirectional"))
    )
    (net (code "30") (name "/DIAG-COL_SW") (class "Default")
      (node (ref "Q4") (pin "4") (pinfunction "DG_4") (pintype "passive"))
      (node (ref "R21") (pin "1") (pinfunction "1_1") (pintype "passive"))
    )
    (net (code "31") (name "/DUE_SW") (class "Default")
      (node (ref "ARQ_TERMINAL") (pin "3") (pinfunction "3_3") (pintype "passive"))
      (node (ref "R18") (pin "1") (pinfunction "1_1") (pintype "passive"))
    )
    (net (code "32") (name "/EEXTINT") (class "Default")
      (node (ref "U1") (pin "25") (pinfunction "PA5_25") (pintype "bidirectional"))
    )
    (net (code "33") (name "/EMDC") (class "Default")
      (node (ref "U1") (pin "123") (pinfunction "PB8_123") (pintype "bidirectional"))
    )
    (net (code "34") (name "/EMDIO") (class "Default")
      (node (ref "U1") (pin "127") (pinfunction "PB9_127") (pintype "bidirectional"))
    )
    (net (code "35") (name "/EN") (class "Default")
      (node (ref "IC2") (pin "4") (pinfunction "EN_4") (pintype "input"))
      (node (ref "R10") (pin "2") (pinfunction "2_2") (pintype "passive"))
    )
    (net (code "36") (name "/ERASE_CMD") (class "Default")
      (node (ref "PROGRAMMER") (pin "5") (pinfunction "5_5") (pintype "passive"))
      (node (ref "T3") (pin "3") (pinfunction "G_3") (pintype "passive"))
    )
    (net (code "37") (name "/ERASE_S") (class "Default")
      (node (ref "ERASE") (pin "2") (pinfunction "2_2") (pintype "passive"))
      (node (ref "T3") (pin "1") (pinfunction "D_1") (pintype "passive"))
      (node (ref "U1") (pin "130") (pinfunction "PC0_130") (pintype "bidirectional"))
    )
    (net (code "38") (name "/ERXD0") (class "Default")
      (node (ref "U1") (pin "120") (pinfunction "PB5_120") (pintype "bidirectional"))
    )
    (net (code "39") (name "/ERXD1") (class "Default")
      (node (ref "U1") (pin "121") (pinfunction "PB6_121") (pintype "bidirectional"))
    )
    (net (code "40") (name "/ERX_DV") (class "Default")
      (node (ref "U1") (pin "119") (pinfunction "PB4_119") (pintype "bidirectional"))
    )
    (net (code "41") (name "/ERX_ER") (class "Default")
      (node (ref "U1") (pin "122") (pinfunction "PB7_122") (pintype "bidirectional"))
    )
    (net (code "42") (name "/ETXD0") (class "Default")
      (node (ref "U1") (pin "115") (pinfunction "PB2_115") (pintype "bidirectional"))
    )
    (net (code "43") (name "/ETXD1") (class "Default")
      (node (ref "U1") (pin "118") (pinfunction "PB3_118") (pintype "bidirectional"))
    )
    (net (code "44") (name "/FB") (class "Default")
      (node (ref "IC2") (pin "3") (pinfunction "FB_3") (pintype "input"))
      (node (ref "R11") (pin "1") (pinfunction "1_1") (pintype "passive"))
      (node (ref "R12") (pin "2") (pinfunction "2_2") (pintype "passive"))
    )
    (net (code "45") (name "/GATE_CMD") (class "Default")
      (node (ref "IC1") (pin "7") (pinfunction "OUT_7") (pintype "output"))
      (node (ref "T1") (pin "3") (pinfunction "G_3") (pintype "passive"))
    )
    (net (code "46") (name "/GNDBU") (class "Default")
      (node (ref "U1") (pin "54") (pinfunction "GNDBU_54") (pintype "power_in"))
    )
    (net (code "47") (name "/JTAG_TCK") (class "Default")
      (node (ref "U1") (pin "28") (pinfunction "PB28_28") (pintype "bidirectional"))
    )
    (net (code "48") (name "/JTAG_TDI") (class "Default")
      (node (ref "U1") (pin "29") (pinfunction "PB29_29") (pintype "bidirectional"))
    )
    (net (code "49") (name "/JTAG_TDO") (class "Default")
      (node (ref "U1") (pin "30") (pinfunction "PB30_30") (pintype "bidirectional"))
    )
    (net (code "50") (name "/JTAG_TMS") (class "Default")
      (node (ref "U1") (pin "31") (pinfunction "PB31_31") (pintype "bidirectional"))
    )
    (net (code "51") (name "/MASTER-RESET") (class "Default")
      (node (ref "PROGRAMMER") (pin "1") (pinfunction "1_1") (pintype "passive"))
      (node (ref "U1") (pin "69") (pinfunction "NRST_69") (pintype "bidirectional"))
    )
    (net (code "52") (name "/MISO") (class "Default")
      (node (ref "RN2") (pin "8") (pinfunction "2_8") (pintype "passive"))
      (node (ref "U$9") (pin "2") (pinfunction "DO_2") (pintype "bidirectional"))
      (node (ref "U1") (pin "108") (pinfunction "PA25_108") (pintype "bidirectional"))
    )
    (net (code "53") (name "/MOSI") (class "Default")
      (node (ref "RN2") (pin "6") (pinfunction "2_6") (pintype "passive"))
      (node (ref "U$9") (pin "6") (pinfunction "DI_6") (pintype "bidirectional"))
      (node (ref "U1") (pin "109") (pinfunction "PA26_109") (pintype "bidirectional"))
    )
    (net (code "54") (name "/N$30") (class "Default")
      (node (ref "U2-C") (pin "5") (pinfunction "VREF_5") (pintype "bidirectional"))
    )
    (net (code "55") (name "/PB0") (class "Default")
      (node (ref "IO1") (pin "2") (pinfunction "2_2") (pintype "passive"))
      (node (ref "U1") (pin "113") (pinfunction "PB0_113") (pintype "bidirectional"))
    )
    (net (code "56") (name "/PB1") (class "Default")
      (node (ref "IO1") (pin "3") (pinfunction "3_3") (pintype "passive"))
      (node (ref "U1") (pin "114") (pinfunction "PB1_114") (pintype "bidirectional"))
    )
    (net (code "57") (name "/PIN22") (class "Default")
      (node (ref "U1") (pin "1") (pinfunction "PB26_1") (pintype "bidirectional"))
    )
    (net (code "58") (name "/PIN23") (class "Default")
      (node (ref "U1") (pin "7") (pinfunction "PA14_7") (pintype "bidirectional"))
    )
    (net (code "59") (name "/PIN24") (class "Default")
      (node (ref "U1") (pin "8") (pinfunction "PA15_8") (pintype "bidirectional"))
    )
    (net (code "60") (name "/PIN25") (class "Default")
      (node (ref "U1") (pin "13") (pinfunction "PD0_13") (pintype "bidirectional"))
    )
    (net (code "61") (name "/PIN26") (class "Default")
      (node (ref "U1") (pin "14") (pinfunction "PD1_14") (pintype "bidirectional"))
    )
    (net (code "62") (name "/PIN27") (class "Default")
      (node (ref "U1") (pin "15") (pinfunction "PD2_15") (pintype "bidirectional"))
    )
    (net (code "63") (name "/PIN28") (class "Default")
      (node (ref "U1") (pin "16") (pinfunction "PD3_16") (pintype "bidirectional"))
    )
    (net (code "64") (name "/PIN29") (class "Default")
      (node (ref "U1") (pin "19") (pinfunction "PD6_19") (pintype "bidirectional"))
    )
    (net (code "65") (name "/PIN30") (class "Default")
      (node (ref "U1") (pin "22") (pinfunction "PD9_22") (pintype "bidirectional"))
    )
    (net (code "66") (name "/PIN31") (class "Default")
      (node (ref "U1") (pin "26") (pinfunction "PA7_26") (pintype "bidirectional"))
    )
    (net (code "67") (name "/PIN32") (class "Default")
      (node (ref "U1") (pin "32") (pinfunction "PD10_32") (pintype "bidirectional"))
    )
    (net (code "68") (name "/PIN33") (class "Default")
      (node (ref "U1") (pin "55") (pinfunction "PC1_55") (pintype "bidirectional"))
    )
    (net (code "69") (name "/PIN34") (class "Default")
      (node (ref "U1") (pin "59") (pinfunction "PC2_59") (pintype "bidirectional"))
    )
    (net (code "70") (name "/PIN35") (class "Default")
      (node (ref "U1") (pin "60") (pinfunction "PC3_60") (pintype "bidirectional"))
    )
    (net (code "71") (name "/PIN36") (class "Default")
      (node (ref "U1") (pin "116") (pinfunction "PC4_116") (pintype "bidirectional"))
    )
    (net (code "72") (name "/PIN37") (class "Default")
      (node (ref "U1") (pin "63") (pinfunction "PC5_63") (pintype "bidirectional"))
    )
    (net (code "73") (name "/PIN38") (class "Default")
      (node (ref "U1") (pin "64") (pinfunction "PC6_64") (pintype "bidirectional"))
    )
    (net (code "74") (name "/PIN39") (class "Default")
      (node (ref "U1") (pin "65") (pinfunction "PC7_65") (pintype "bidirectional"))
    )
    (net (code "75") (name "/PIN40") (class "Default")
      (node (ref "U1") (pin "66") (pinfunction "PC8_66") (pintype "bidirectional"))
    )
    (net (code "76") (name "/PIN41") (class "Default")
      (node (ref "U1") (pin "67") (pinfunction "PC9_67") (pintype "bidirectional"))
    )
    (net (code "77") (name "/PIN42") (class "Default")
      (node (ref "U1") (pin "71") (pinfunction "PA19_71") (pintype "bidirectional"))
    )
    (net (code "78") (name "/PIN43") (class "Default")
      (node (ref "U1") (pin "72") (pinfunction "PA20_72") (pintype "bidirectional"))
    )
    (net (code "79") (name "/PIN45") (class "Default")
      (node (ref "U1") (pin "100") (pinfunction "PC18_100") (pintype "bidirectional"))
    )
    (net (code "80") (name "/PIN46") (class "Default")
      (node (ref "C19") (pin "1") (pinfunction "1_1") (pintype "passive"))
      (node (ref "RG") (pin "2") (pinfunction "2_2") (pintype "passive"))
      (node (ref "U1") (pin "99") (pinfunction "PC17_99") (pintype "bidirectional"))
    )
    (net (code "81") (name "/PIN47") (class "Default")
      (node (ref "U1") (pin "98") (pinfunction "PC16_98") (pintype "bidirectional"))
    )
    (net (code "82") (name "/PIN48") (class "Default")
      (node (ref "RN1") (pin "1") (pinfunction "1_1") (pintype "passive"))
      (node (ref "U1") (pin "97") (pinfunction "PC15_97") (pintype "bidirectional"))
    )
    (net (code "83") (name "/PIN49") (class "Default")
      (node (ref "RN1") (pin "2") (pinfunction "1_2") (pintype "passive"))
      (node (ref "U1") (pin "96") (pinfunction "PC14_96") (pintype "bidirectional"))
    )
    (net (code "84") (name "/PIN50") (class "Default")
      (node (ref "RN1") (pin "3") (pinfunction "1_3") (pintype "passive"))
      (node (ref "U1") (pin "95") (pinfunction "PC13_95") (pintype "bidirectional"))
    )
    (net (code "85") (name "/PIN51") (class "Default")
      (node (ref "RN1") (pin "4") (pinfunction "1_4") (pintype "passive"))
      (node (ref "U1") (pin "94") (pinfunction "PC12_94") (pintype "bidirectional"))
    )
    (net (code "86") (name "/PWM2") (class "Default")
      (node (ref "U1") (pin "144") (pinfunction "PB25_144") (pintype "bidirectional"))
    )
    (net (code "87") (name "/PWM3") (class "Default")
      (node (ref "U1") (pin "139") (pinfunction "PC28_139") (pintype "bidirectional"))
    )
    (net (code "88") (name "/PWM5") (class "Default")
      (node (ref "U1") (pin "136") (pinfunction "PC25_136") (pintype "bidirectional"))
    )
    (net (code "89") (name "/PWM6") (class "Default")
      (node (ref "U1") (pin "135") (pinfunction "PC24_135") (pintype "bidirectional"))
    )
    (net (code "90") (name "/PWM7") (class "Default")
      (node (ref "U1") (pin "134") (pinfunction "PC23_134") (pintype "bidirectional"))
    )
    (net (code "91") (name "/PWM8") (class "Default")
      (node (ref "U1") (pin "133") (pinfunction "PC22_133") (pintype "bidirectional"))
    )
    (net (code "92") (name "/PWM9") (class "Default")
      (node (ref "U1") (pin "132") (pinfunction "PC21_132") (pintype "bidirectional"))
    )
    (net (code "93") (name "/PWM11") (class "Default")
      (node (ref "U1") (pin "20") (pinfunction "PD7_20") (pintype "bidirectional"))
    )
    (net (code "94") (name "/PWM12") (class "Default")
      (node (ref "U1") (pin "21") (pinfunction "PD8_21") (pintype "bidirectional"))
    )
    (net (code "95") (name "/PWM13") (class "Default")
      (node (ref "U1") (pin "68") (pinfunction "PB27_68") (pintype "bidirectional"))
    )
    (net (code "96") (name "/RXD0") (class "Default")
      (node (ref "SERIAL0") (pin "1") (pinfunction "1_1") (pintype "passive"))
      (node (ref "U1") (pin "18") (pinfunction "PD5_18") (pintype "bidirectional"))
    )
    (net (code "97") (name "/RXD1") (class "Default")
      (node (ref "SERIAL1") (pin "1") (pinfunction "1_1") (pintype "passive"))
      (node (ref "U1") (pin "5") (pinfunction "PA12_5") (pintype "bidirectional"))
    )
    (net (code "98") (name "/RXL") (class "Default")
      (node (ref "U1") (pin "103") (pinfunction "PC30_103") (pintype "bidirectional"))
    )
    (net (code "99") (name "/RX_ARQ") (class "Default")
      (node (ref "ARQ_TERMINAL") (pin "2") (pinfunction "2_2") (pintype "passive"))
      (node (ref "MAX3232") (pin "14") (pinfunction "DOUT1_14") (pintype "output"))
    )
    (net (code "100") (name "/RX_DUE") (class "Default")
      (node (ref "ARQ_TERMINAL") (pin "6") (pinfunction "6_6") (pintype "passive"))
      (node (ref "R1") (pin "2") (pinfunction "2_2") (pintype "passive"))
      (node (ref "R9") (pin "2") (pinfunction "2_2") (pintype "passive"))
      (node (ref "U1") (pin "3") (pinfunction "PA10_3") (pintype "bidirectional"))
    )
    (net (code "101") (name "/RX_DUE1") (class "Default")
      (node (ref "MAX3232") (pin "12") (pinfunction "ROUT1_12") (pintype "output"))
      (node (ref "R1") (pin "1") (pinfunction "1_1") (pintype "passive"))
    )
    (net (code "102") (name "/RX_PROG") (class "Default")
      (node (ref "PROGRAMMER") (pin "3") (pinfunction "3_3") (pintype "passive"))
      (node (ref "R17") (pin "1") (pinfunction "1_1") (pintype "passive"))
      (node (ref "T8") (pin "3") (pinfunction "D_3") (pintype "passive"))
    )
    (net (code "103") (name "/RX_SAM") (class "Default")
      (node (ref "BT") (pin "4") (pinfunction "4_4") (pintype "passive"))
      (node (ref "R8") (pin "1") (pinfunction "1_1") (pintype "passive"))
      (node (ref "TP4") (pin "P$1") (pinfunction "1_P$1") (pintype "bidirectional"))
      (node (ref "U1") (pin "27") (pinfunction "PA8_27") (pintype "bidirectional"))
    )
    (net (code "104") (name "/SCL0-3") (class "Default")
      (node (ref "R3") (pin "1") (pinfunction "1_1") (pintype "passive"))
      (node (ref "U1") (pin "87") (pinfunction "PB13_87") (pintype "bidirectional"))
      (node (ref "U4") (pin "5") (pinfunction "SCL_5") (pintype "bidirectional"))
    )
    (net (code "105") (name "/SCL1") (class "Default")
      (node (ref "RTC") (pin "3") (pinfunction "3_3") (pintype "passive"))
      (node (ref "U1") (pin "70") (pinfunction "PA18_70") (pintype "bidirectional"))
    )
    (net (code "106") (name "/SDA0-3") (class "Default")
      (node (ref "R6") (pin "2") (pinfunction "2_2") (pintype "passive"))
      (node (ref "U1") (pin "86") (pinfunction "PB12_86") (pintype "bidirectional"))
      (node (ref "U4") (pin "6") (pinfunction "SDA_6") (pintype "bidirectional"))
    )
    (net (code "107") (name "/SDA1") (class "Default")
      (node (ref "RTC") (pin "2") (pinfunction "2_2") (pintype "passive"))
      (node (ref "U1") (pin "9") (pinfunction "PA17_9") (pintype "bidirectional"))
    )
    (net (code "108") (name "/SPCK") (class "Default")
      (node (ref "RN2") (pin "7") (pinfunction "2_7") (pintype "passive"))
      (node (ref "U$9") (pin "4") (pinfunction "SCK_4") (pintype "bidirectional"))
      (node (ref "U1") (pin "110") (pinfunction "PA27_110") (pintype "bidirectional"))
    )
    (net (code "109") (name "/SS3") (class "Default")
      (node (ref "RN2") (pin "5") (pinfunction "2_5") (pintype "passive"))
      (node (ref "U$9") (pin "7") (pinfunction "CS_7") (pintype "bidirectional"))
      (node (ref "U1") (pin "142") (pinfunction "PB23_142") (pintype "bidirectional"))
    )
    (net (code "110") (name "/SW") (class "Default")
      (node (ref "C42") (pin "2") (pinfunction "2_2") (pintype "passive"))
      (node (ref "D4") (pin "P$1") (pinfunction "K_P$1") (pintype "bidirectional"))
      (node (ref "IC2") (pin "6") (pinfunction "SW_6") (pintype "output"))
      (node (ref "L4") (pin "P$1") (pinfunction "1_P$1") (pintype "passive"))
    )
    (net (code "111") (name "/TXD0") (class "Default")
      (node (ref "SERIAL0") (pin "2") (pinfunction "2_2") (pintype "passive"))
      (node (ref "U1") (pin "17") (pinfunction "PD4_17") (pintype "bidirectional"))
    )
    (net (code "112") (name "/TXD1") (class "Default")
      (node (ref "SERIAL1") (pin "2") (pinfunction "2_2") (pintype "passive"))
      (node (ref "U1") (pin "6") (pinfunction "PA13_6") (pintype "bidirectional"))
    )
    (net (code "113") (name "/TXL") (class "Default")
      (node (ref "U1") (pin "107") (pinfunction "PA21_107") (pintype "bidirectional"))
    )
    (net (code "114") (name "/TX_ARQ") (class "Default")
      (node (ref "ARQ_TERMINAL") (pin "1") (pinfunction "1_1") (pintype "passive"))
      (node (ref "MAX3232") (pin "13") (pinfunction "RIN1_13") (pintype "input"))
    )
    (net (code "115") (name "/TX_DUE") (class "Default")
      (node (ref "ARQ_TERMINAL") (pin "5") (pinfunction "5_5") (pintype "passive"))
      (node (ref "R13") (pin "2") (pinfunction "2_2") (pintype "passive"))
      (node (ref "R2") (pin "2") (pinfunction "2_2") (pintype "passive"))
      (node (ref "U1") (pin "4") (pinfunction "PA11_4") (pintype "bidirectional"))
    )
    (net (code "116") (name "/TX_DUE1") (class "Default")
      (node (ref "MAX3232") (pin "11") (pinfunction "DIN1_11") (pintype "input"))
      (node (ref "R2") (pin "1") (pinfunction "1_1") (pintype "passive"))
    )
    (net (code "117") (name "/TX_PROG") (class "Default")
      (node (ref "PROGRAMMER") (pin "2") (pinfunction "2_2") (pintype "passive"))
      (node (ref "R16") (pin "1") (pinfunction "1_1") (pintype "passive"))
      (node (ref "T7") (pin "3") (pinfunction "D_3") (pintype "passive"))
    )
    (net (code "118") (name "/TX_SAM") (class "Default")
      (node (ref "BT") (pin "5") (pinfunction "5_5") (pintype "passive"))
      (node (ref "T7") (pin "2") (pinfunction "S_2") (pintype "passive"))
      (node (ref "TP3") (pin "P$1") (pinfunction "1_P$1") (pintype "bidirectional"))
      (node (ref "U1") (pin "2") (pinfunction "PA9_2") (pintype "bidirectional"))
    )
    (net (code "119") (name "/UOTGID") (class "Default")
      (node (ref "U1") (pin "129") (pinfunction "PB11_129") (pintype "bidirectional"))
    )
    (net (code "120") (name "/UOTGVBOF") (class "Default")
      (node (ref "U1") (pin "128") (pinfunction "PB10_128") (pintype "bidirectional"))
    )
    (net (code "121") (name "/USBVCC") (class "Default")
      (node (ref "PROGRAMMER") (pin "4") (pinfunction "4_4") (pintype "passive"))
      (node (ref "T1") (pin "1") (pinfunction "D_1") (pintype "passive"))
    )
    (net (code "122") (name "/VBG") (class "Default")
      (node (ref "C25") (pin "1") (pinfunction "1_1") (pintype "passive"))
      (node (ref "R7") (pin "2") (pinfunction "2_2") (pintype "passive"))
      (node (ref "U1") (pin "40") (pinfunction "VBG_40") (pintype "passive"))
    )
    (net (code "123") (name "/VDDANA") (class "Default")
      (node (ref "C10") (pin "2") (pinfunction "2_2") (pintype "passive"))
      (node (ref "C3") (pin "+") (pinfunction "+_+") (pintype "passive"))
      (node (ref "L1") (pin "2") (pinfunction "2_2") (pintype "passive"))
      (node (ref "U1") (pin "73") (pinfunction "VDDANA_73") (pintype "power_in"))
    )
    (net (code "124") (name "/VDDBU") (class "Default")
      (node (ref "U1") (pin "52") (pinfunction "VDDBU_52") (pintype "power_in"))
    )
    (net (code "125") (name "/VDDOUT") (class "Default")
      (node (ref "C11") (pin "+") (pinfunction "+_+") (pintype "passive"))
      (node (ref "C12") (pin "2") (pinfunction "2_2") (pintype "passive"))
      (node (ref "C13") (pin "2") (pinfunction "2_2") (pintype "passive"))
      (node (ref "C14") (pin "2") (pinfunction "2_2") (pintype "passive"))
      (node (ref "C15") (pin "2") (pinfunction "2_2") (pintype "passive"))
      (node (ref "C16") (pin "2") (pinfunction "2_2") (pintype "passive"))
      (node (ref "C17") (pin "2") (pinfunction "2_2") (pintype "passive"))
      (node (ref "L5") (pin "1") (pinfunction "1_1") (pintype "passive"))
      (node (ref "U1") (pin "10") (pinfunction "VDDCORE1_10") (pintype "input"))
      (node (ref "U1") (pin "104") (pinfunction "VDDCORE4_104") (pintype "input"))
      (node (ref "U1") (pin "124") (pinfunction "VDDCORE5_124") (pintype "input"))
      (node (ref "U1") (pin "45") (pinfunction "VDDCORE2_45") (pintype "input"))
      (node (ref "U1") (pin "56") (pinfunction "VDDOUT_56") (pintype "output"))
      (node (ref "U1") (pin "61") (pinfunction "VDDCORE3_61") (pintype "input"))
    )
    (net (code "126") (name "/VDDOUTMI") (class "Default")
      (node (ref "C2") (pin "+") (pinfunction "+_+") (pintype "passive"))
      (node (ref "C9") (pin "2") (pinfunction "2_2") (pintype "passive"))
      (node (ref "L2") (pin "2") (pinfunction "2_2") (pintype "passive"))
      (node (ref "U1") (pin "41") (pinfunction "VDDUTMI_41") (pintype "input"))
    )
    (net (code "127") (name "/VDDPLL") (class "Default")
      (node (ref "C32") (pin "2") (pinfunction "2_2") (pintype "passive"))
      (node (ref "C33") (pin "+") (pinfunction "+_+") (pintype "passive"))
      (node (ref "L5") (pin "2") (pinfunction "2_2") (pintype "passive"))
      (node (ref "U1") (pin "34") (pinfunction "VDDPLL_34") (pintype "input"))
    )
    (net (code "128") (name "/VIN") (class "Default")
      (node (ref "F1") (pin "2") (pinfunction "2_2") (pintype "bidirectional"))
      (node (ref "JP2") (pin "2") (pinfunction "2_2") (pintype "passive"))
      (node (ref "U2") (pin "3") (pinfunction "OUT_3") (pintype "bidirectional"))
    )
    (net (code "129") (name "/VIN_DUE") (class "Default")
      (node (ref "C41") (pin "+") (pinfunction "+_+") (pintype "passive"))
      (node (ref "D1") (pin "C") (pinfunction "C_C") (pintype "passive"))
      (node (ref "F1") (pin "1") (pinfunction "1_1") (pintype "bidirectional"))
      (node (ref "IC2") (pin "5") (pinfunction "VIN_5") (pintype "input"))
      (node (ref "PC1") (pin "+") (pinfunction "+_+") (pintype "passive"))
      (node (ref "R10") (pin "1") (pinfunction "1_1") (pintype "passive"))
      (node (ref "RN4") (pin "6") (pinfunction "2_6") (pintype "passive"))
    )
    (net (code "130") (name "/XIN") (class "Default")
      (node (ref "C22") (pin "1") (pinfunction "1_1") (pintype "passive"))
      (node (ref "U1") (pin "36") (pinfunction "XIN_36") (pintype "input"))
      (node (ref "Y1") (pin "1") (pinfunction "C1_1") (pintype "passive"))
    )
    (net (code "131") (name "/XIN32") (class "Default")
      (node (ref "C24") (pin "1") (pinfunction "1_1") (pintype "passive"))
      (node (ref "U1") (pin "48") (pinfunction "XIN32_48") (pintype "output"))
      (node (ref "Y2") (pin "P$2") (pinfunction "2_P$2") (pintype "bidirectional"))
    )
    (net (code "132") (name "/XOUT") (class "Default")
      (node (ref "C21") (pin "1") (pinfunction "1_1") (pintype "passive"))
      (node (ref "U1") (pin "35") (pinfunction "XOUT_35") (pintype "output"))
      (node (ref "Y1") (pin "3") (pinfunction "C2_3") (pintype "passive"))
    )
    (net (code "133") (name "/XOUT32") (class "Default")
      (node (ref "C23") (pin "1") (pinfunction "1_1") (pintype "passive"))
      (node (ref "U1") (pin "49") (pinfunction "XOUT32_49") (pintype "output"))
      (node (ref "Y2") (pin "P$1") (pinfunction "1_P$1") (pintype "bidirectional"))
    )
    (net (code "134") (name "GND") (class "Default")
      (node (ref "ARQ_TERMINAL") (pin "4") (pinfunction "4_4") (pintype "passive"))
      (node (ref "BT") (pin "3") (pinfunction "3_3") (pintype "passive"))
      (node (ref "C1") (pin "-") (pinfunction "-_-") (pintype "passive"))
      (node (ref "C1-C") (pin "2") (pinfunction "2_2") (pintype "passive"))
      (node (ref "C10") (pin "1") (pinfunction "1_1") (pintype "passive"))
      (node (ref "C11") (pin "-") (pinfunction "-_-") (pintype "passive"))
      (node (ref "C12") (pin "1") (pinfunction "1_1") (pintype "passive"))
      (node (ref "C13") (pin "1") (pinfunction "1_1") (pintype "passive"))
      (node (ref "C14") (pin "1") (pinfunction "1_1") (pintype "passive"))
      (node (ref "C15") (pin "1") (pinfunction "1_1") (pintype "passive"))
      (node (ref "C16") (pin "1") (pinfunction "1_1") (pintype "passive"))
      (node (ref "C17") (pin "1") (pinfunction "1_1") (pintype "passive"))
      (node (ref "C18") (pin "1") (pinfunction "1_1") (pintype "passive"))
      (node (ref "C19") (pin "2") (pinfunction "2_2") (pintype "passive"))
      (node (ref "C2") (pin "-") (pinfunction "-_-") (pintype "passive"))
      (node (ref "C20") (pin "2") (pinfunction "P$2_2") (pintype "passive"))
      (node (ref "C21") (pin "2") (pinfunction "2_2") (pintype "passive"))
      (node (ref "C22") (pin "2") (pinfunction "2_2") (pintype "passive"))
      (node (ref "C23") (pin "2") (pinfunction "2_2") (pintype "passive"))
      (node (ref "C24") (pin "2") (pinfunction "2_2") (pintype "passive"))
      (node (ref "C25") (pin "2") (pinfunction "2_2") (pintype "passive"))
      (node (ref "C29") (pin "-") (pinfunction "-_-") (pintype "passive"))
      (node (ref "C3") (pin "-") (pinfunction "-_-") (pintype "passive"))
      (node (ref "C30") (pin "1") (pinfunction "1_1") (pintype "passive"))
      (node (ref "C31") (pin "1") (pinfunction "1_1") (pintype "passive"))
      (node (ref "C32") (pin "1") (pinfunction "1_1") (pintype "passive"))
      (node (ref "C33") (pin "-") (pinfunction "-_-") (pintype "passive"))
      (node (ref "C38") (pin "1") (pinfunction "1_1") (pintype "passive"))
      (node (ref "C39") (pin "2") (pinfunction "2_2") (pintype "passive"))
      (node (ref "C4") (pin "1") (pinfunction "1_1") (pintype "passive"))
      (node (ref "C41") (pin "-") (pinfunction "-_-") (pintype "passive"))
      (node (ref "C5") (pin "1") (pinfunction "1_1") (pintype "passive"))
      (node (ref "C6") (pin "1") (pinfunction "1_1") (pintype "passive"))
      (node (ref "C7") (pin "1") (pinfunction "1_1") (pintype "passive"))
      (node (ref "C8") (pin "1") (pinfunction "1_1") (pintype "passive"))
      (node (ref "C9") (pin "1") (pinfunction "1_1") (pintype "passive"))
      (node (ref "D1") (pin "A") (pinfunction "A_A") (pintype "passive"))
      (node (ref "D4") (pin "P$2") (pinfunction "A_P$2") (pintype "bidirectional"))
      (node (ref "D5") (pin "A") (pinfunction "A_A") (pintype "passive"))
      (node (ref "IC1") (pin "4") (pinfunction "V-_4") (pintype "power_in"))
      (node (ref "IC2") (pin "2") (pinfunction "GND_2") (pintype "power_in"))
      (node (ref "IC4") (pin "1") (pinfunction "GND/ADJ_1") (pintype "input"))
      (node (ref "IO1") (pin "1") (pinfunction "1_1") (pintype "passive"))
      (node (ref "LED1") (pin "C") (pinfunction "C_C") (pintype "passive"))
      (node (ref "LED2") (pin "C") (pinfunction "C_C") (pintype "passive"))
      (node (ref "LED3") (pin "C") (pinfunction "C_C") (pintype "passive"))
      (node (ref "LED4") (pin "C") (pinfunction "C_C") (pintype "passive"))
      (node (ref "MAX3232") (pin "15") (pinfunction "GND_15") (pintype "passive"))
      (node (ref "PC1") (pin "-") (pinfunction "-_-") (pintype "passive"))
      (node (ref "PC2") (pin "-") (pinfunction "-_-") (pintype "passive"))
      (node (ref "PROGRAMMER") (pin "6") (pinfunction "6_6") (pintype "passive"))
      (node (ref "Q4") (pin "1") (pinfunction "GND_1") (pintype "passive"))
      (node (ref "R11") (pin "2") (pinfunction "2_2") (pintype "passive"))
      (node (ref "R14") (pin "1") (pinfunction "1_1") (pintype "passive"))
      (node (ref "R15") (pin "1") (pinfunction "1_1") (pintype "passive"))
      (node (ref "R22") (pin "1") (pinfunction "1_1") (pintype "passive"))
      (node (ref "R23") (pin "1") (pinfunction "1_1") (pintype "passive"))
      (node (ref "R7") (pin "1") (pinfunction "1_1") (pintype "passive"))
      (node (ref "RG") (pin "3") (pinfunction "3_3") (pintype "passive"))
      (node (ref "RN4") (pin "2") (pinfunction "1_2") (pintype "passive"))
      (node (ref "RN4") (pin "5") (pinfunction "2_5") (pintype "passive"))
      (node (ref "RN4") (pin "7") (pinfunction "2_7") (pintype "passive"))
      (node (ref "RTC") (pin "5") (pinfunction "5_5") (pintype "passive"))
      (node (ref "SERIAL0") (pin "3") (pinfunction "3_3") (pintype "passive"))
      (node (ref "SERIAL1") (pin "3") (pinfunction "3_3") (pintype "passive"))
      (node (ref "U$9") (pin "3") (pinfunction "GND_3") (pintype "bidirectional"))
      (node (ref "U$9") (pin "SHIELD@1") (pinfunction "SHIELD_SHIELD@1") (pintype "bidirectional"))
      (node (ref "U$9") (pin "SHIELD@2") (pinfunction "SHIELD_SHIELD@2") (pintype "bidirectional"))
      (node (ref "U$9") (pin "SHIELD@3") (pinfunction "SHIELD_SHIELD@3") (pintype "bidirectional"))
      (node (ref "U$9") (pin "SHIELD@4") (pinfunction "SHIELD_SHIELD@4") (pintype "bidirectional"))
      (node (ref "U$9") (pin "SHIELD@5") (pinfunction "SHIELD_SHIELD@5") (pintype "bidirectional"))
      (node (ref "U1") (pin "106") (pinfunction "GND3_106") (pintype "power_in"))
      (node (ref "U1") (pin "12") (pinfunction "GND1_12") (pintype "power_in"))
      (node (ref "U1") (pin "126") (pinfunction "GND4_126") (pintype "power_in"))
      (node (ref "U1") (pin "33") (pinfunction "GNDPLL_33") (pintype "power_in"))
      (node (ref "U1") (pin "44") (pinfunction "GNDUTMI_44") (pintype "power_in"))
      (node (ref "U1") (pin "46") (pinfunction "JTAGSEL_46") (pintype "input"))
      (node (ref "U1") (pin "51") (pinfunction "TST_51") (pintype "input"))
      (node (ref "U1") (pin "58") (pinfunction "GND2_58") (pintype "power_in"))
      (node (ref "U1") (pin "74") (pinfunction "GNDANA_74") (pintype "power_in"))
      (node (ref "U1") (pin "75") (pinfunction "ADVREF_75") (pintype "power_in"))
      (node (ref "U2") (pin "1") (pinfunction "GND_1") (pintype "bidirectional"))
      (node (ref "U2-C") (pin "2") (pinfunction "GND_2") (pintype "bidirectional"))
      (node (ref "U2-C1") (pin "3") (pinfunction "3_3") (pintype "output"))
      (node (ref "U4") (pin "3") (pinfunction "GND_3") (pintype "bidirectional"))
      (node (ref "X11") (pin "1") (pinfunction "KL_1") (pintype "passive"))
      (node (ref "X2") (pin "2") (pinfunction "KL_2") (pintype "passive"))
      (node (ref "X3") (pin "1") (pinfunction "KL_1") (pintype "passive"))
      (node (ref "X4") (pin "1") (pinfunction "KL_1") (pintype "passive"))
      (node (ref "X5") (pin "2") (pinfunction "KL_2") (pintype "passive"))
      (node (ref "X6") (pin "2") (pinfunction "KL_2") (pintype "passive"))
      (node (ref "X7") (pin "1") (pinfunction "KL_1") (pintype "passive"))
      (node (ref "Y1") (pin "2") (pinfunction "GND_2") (pintype "passive"))
      (node (ref "Y1") (pin "4") (pinfunction "GND_4") (pintype "passive"))
    )
    (net (code "135") (name "Net-(C1-C-Pad1)") (class "Default")
      (node (ref "C1-C") (pin "1") (pinfunction "1_1") (pintype "passive"))
      (node (ref "R1-C5") (pin "1") (pinfunction "1_1") (pintype "passive"))
      (node (ref "R2-C") (pin "2") (pinfunction "2_2") (pintype "passive"))
    )
    (net (code "136") (name "Net-(MAX3232-C1+)") (class "Default")
      (node (ref "C35") (pin "1") (pinfunction "1_1") (pintype "passive"))
      (node (ref "MAX3232") (pin "1") (pinfunction "C1+_1") (pintype "input"))
    )
    (net (code "137") (name "Net-(MAX3232-C1-)") (class "Default")
      (node (ref "C35") (pin "2") (pinfunction "2_2") (pintype "passive"))
      (node (ref "MAX3232") (pin "3") (pinfunction "C1-_3") (pintype "input"))
    )
    (net (code "138") (name "Net-(MAX3232-C2+)") (class "Default")
      (node (ref "C36") (pin "1") (pinfunction "1_1") (pintype "passive"))
      (node (ref "MAX3232") (pin "4") (pinfunction "C2+_4") (pintype "input"))
    )
    (net (code "139") (name "Net-(MAX3232-C2-)") (class "Default")
      (node (ref "C36") (pin "2") (pinfunction "2_2") (pintype "passive"))
      (node (ref "MAX3232") (pin "5") (pinfunction "C2-_5") (pintype "input"))
    )
    (net (code "140") (name "Net-(MAX3232-V+)") (class "Default")
      (node (ref "C37") (pin "2") (pinfunction "2_2") (pintype "passive"))
      (node (ref "MAX3232") (pin "2") (pinfunction "V+_2") (pintype "power_in"))
    )
    (net (code "141") (name "Net-(MAX3232-V-)") (class "Default")
      (node (ref "C38") (pin "2") (pinfunction "2_2") (pintype "passive"))
      (node (ref "MAX3232") (pin "6") (pinfunction "V-_6") (pintype "power_in"))
    )
    (net (code "142") (name "Net-(Q1-B)") (class "Default")
      (node (ref "Q1") (pin "1") (pinfunction "B_1") (pintype "passive"))
      (node (ref "R9") (pin "1") (pinfunction "1_1") (pintype "passive"))
    )
    (net (code "143") (name "Net-(Q1-C)") (class "Default")
      (node (ref "Q1") (pin "3") (pinfunction "C_3") (pintype "passive"))
      (node (ref "RX_DUE") (pin "A") (pinfunction "A_A") (pintype "passive"))
    )
    (net (code "144") (name "Net-(Q2-B)") (class "Default")
      (node (ref "Q2") (pin "1") (pinfunction "B_1") (pintype "passive"))
      (node (ref "R13") (pin "1") (pinfunction "1_1") (pintype "passive"))
    )
    (net (code "145") (name "Net-(Q2-C)") (class "Default")
      (node (ref "Q2") (pin "3") (pinfunction "C_3") (pintype "passive"))
      (node (ref "TX_DUE") (pin "A") (pinfunction "A_A") (pintype "passive"))
    )
    (net (code "146") (name "Net-(Q4-IN)") (class "Default")
      (node (ref "Q4") (pin "2") (pinfunction "IN_2") (pintype "passive"))
      (node (ref "R5") (pin "2") (pinfunction "2_2") (pintype "passive"))
    )
    (net (code "147") (name "Net-(Q4-OUT)") (class "Default")
      (node (ref "FUSE1") (pin "1") (pinfunction "1_1") (pintype "passive"))
      (node (ref "Q4") (pin "5") (pinfunction "OUT_5") (pintype "passive"))
    )
    (net (code "148") (name "Net-(R14-Pad2)") (class "Default")
      (node (ref "R14") (pin "2") (pinfunction "2_2") (pintype "passive"))
      (node (ref "TX_DUE") (pin "C") (pinfunction "C_C") (pintype "passive"))
    )
    (net (code "149") (name "Net-(R15-Pad2)") (class "Default")
      (node (ref "R15") (pin "2") (pinfunction "2_2") (pintype "passive"))
      (node (ref "RX_DUE") (pin "C") (pinfunction "C_C") (pintype "passive"))
    )
    (net (code "150") (name "Net-(RN1A-2)") (class "Default")
      (node (ref "LED1") (pin "A") (pinfunction "A_A") (pintype "passive"))
      (node (ref "RN1") (pin "8") (pinfunction "2_8") (pintype "passive"))
    )
    (net (code "151") (name "Net-(RN1B-2)") (class "Default")
      (node (ref "LED2") (pin "A") (pinfunction "A_A") (pintype "passive"))
      (node (ref "RN1") (pin "7") (pinfunction "2_7") (pintype "passive"))
    )
    (net (code "152") (name "Net-(RN1C-2)") (class "Default")
      (node (ref "LED3") (pin "A") (pinfunction "A_A") (pintype "passive"))
      (node (ref "RN1") (pin "6") (pinfunction "2_6") (pintype "passive"))
    )
    (net (code "153") (name "Net-(RN1D-2)") (class "Default")
      (node (ref "LED4") (pin "A") (pinfunction "A_A") (pintype "passive"))
      (node (ref "RN1") (pin "5") (pinfunction "2_5") (pintype "passive"))
    )
    (net (code "154") (name "Net-(T8-S)") (class "Default")
      (node (ref "R8") (pin "2") (pinfunction "2_2") (pintype "passive"))
      (node (ref "T8") (pin "2") (pinfunction "S_2") (pintype "passive"))
    )
    (net (code "155") (name "Net-(U1-FWUP)") (class "Default")
      (node (ref "R4") (pin "1") (pinfunction "1_1") (pintype "passive"))
      (node (ref "U1") (pin "53") (pinfunction "FWUP_53") (pintype "input"))
    )
    (net (code "156") (name "Net-(U2-IN)") (class "Default")
      (node (ref "R18") (pin "2") (pinfunction "2_2") (pintype "passive"))
      (node (ref "U2") (pin "2") (pinfunction "IN_2") (pintype "bidirectional"))
    )
    (net (code "157") (name "Net-(U4-A0)") (class "Default")
      (node (ref "R22") (pin "2") (pinfunction "2_2") (pintype "passive"))
      (node (ref "SJ4") (pin "2") (pinfunction "2_2") (pintype "passive"))
      (node (ref "U4") (pin "7") (pinfunction "A0_7") (pintype "bidirectional"))
    )
    (net (code "158") (name "Net-(U4-A1)") (class "Default")
      (node (ref "R23") (pin "2") (pinfunction "2_2") (pintype "passive"))
      (node (ref "SJ3") (pin "2") (pinfunction "2_2") (pintype "passive"))
      (node (ref "U4") (pin "8") (pinfunction "A1_8") (pintype "bidirectional"))
    )
    (net (code "159") (name "XUSB") (class "Default")
      (node (ref "U1") (pin "39") (pinfunction "VBUS_39") (pintype "power_in"))
    )
    (net (code "160") (name "unconnected-(BT-Pad1)") (class "Default")
      (node (ref "BT") (pin "1") (pinfunction "1_1") (pintype "passive"))
    )
    (net (code "161") (name "unconnected-(BT-Pad6)") (class "Default")
      (node (ref "BT") (pin "6") (pinfunction "6_6") (pintype "passive"))
    )
    (net (code "162") (name "unconnected-(MAX3232-DIN2-Pad10)") (class "Default")
      (node (ref "MAX3232") (pin "10") (pinfunction "DIN2_10") (pintype "input"))
    )
    (net (code "163") (name "unconnected-(MAX3232-DOUT2-Pad7)") (class "Default")
      (node (ref "MAX3232") (pin "7") (pinfunction "DOUT2_7") (pintype "output"))
    )
    (net (code "164") (name "unconnected-(MAX3232-RIN2-Pad8)") (class "Default")
      (node (ref "MAX3232") (pin "8") (pinfunction "RIN2_8") (pintype "input"))
    )
    (net (code "165") (name "unconnected-(MAX3232-ROUT2-Pad9)") (class "Default")
      (node (ref "MAX3232") (pin "9") (pinfunction "ROUT2_9") (pintype "output"))
    )
    (net (code "166") (name "unconnected-(RTC-Pad4)") (class "Default")
      (node (ref "RTC") (pin "4") (pinfunction "4_4") (pintype "passive"))
    )
    (net (code "167") (name "unconnected-(U$9-NC-Pad1)") (class "Default")
      (node (ref "U$9") (pin "1") (pinfunction "NC_1") (pintype "bidirectional"))
    )
    (net (code "168") (name "unconnected-(U$9-PadCD1)") (class "Default")
      (node (ref "U$9") (pin "CD1") (pinfunction "CD1_CD1") (pintype "bidirectional"))
    )
    (net (code "169") (name "unconnected-(U$9-PadCD2)") (class "Default")
      (node (ref "U$9") (pin "CD2") (pinfunction "CD2_CD2") (pintype "bidirectional"))
    )
    (net (code "170") (name "unconnected-(U$9-RSV-Pad8)") (class "Default")
      (node (ref "U$9") (pin "8") (pinfunction "RSV_8") (pintype "bidirectional"))
    )
    (net (code "171") (name "unconnected-(U1-DFSDM-Pad43)") (class "Default")
      (node (ref "U1") (pin "43") (pinfunction "DFSDM_43") (pintype "input"))
    )
    (net (code "172") (name "unconnected-(U1-DFSDP-Pad42)") (class "Default")
      (node (ref "U1") (pin "42") (pinfunction "DFSDP_42") (pintype "input"))
    )
    (net (code "173") (name "unconnected-(U1-DHSDM-Pad38)") (class "Default")
      (node (ref "U1") (pin "38") (pinfunction "DHSDM_38") (pintype "bidirectional"))
    )
    (net (code "174") (name "unconnected-(U1-DHSDP-Pad37)") (class "Default")
      (node (ref "U1") (pin "37") (pinfunction "DHSDP_37") (pintype "bidirectional"))
    )
    (net (code "175") (name "unconnected-(U1-NRSTB-Pad47)") (class "Default")
      (node (ref "U1") (pin "47") (pinfunction "NRSTB_47") (pintype "input"))
    )
    (net (code "176") (name "unconnected-(U1-PA28-Pad111)") (class "Default")
      (node (ref "U1") (pin "111") (pinfunction "PA28_111") (pintype "bidirectional"))
    )
    (net (code "177") (name "unconnected-(U1-PA29-Pad112)") (class "Default")
      (node (ref "U1") (pin "112") (pinfunction "PA29_112") (pintype "bidirectional"))
    )
    (net (code "178") (name "unconnected-(U1-PB22-Pad141)") (class "Default")
      (node (ref "U1") (pin "141") (pinfunction "PB22_141") (pintype "bidirectional"))
    )
    (net (code "179") (name "unconnected-(U1-PB24-Pad143)") (class "Default")
      (node (ref "U1") (pin "143") (pinfunction "PB24_143") (pintype "bidirectional"))
    )
    (net (code "180") (name "unconnected-(U1-PC10-Pad117)") (class "Default")
      (node (ref "U1") (pin "117") (pinfunction "PC10_117") (pintype "bidirectional"))
    )
    (net (code "181") (name "unconnected-(U1-PC11-Pad93)") (class "Default")
      (node (ref "U1") (pin "93") (pinfunction "PC11_93") (pintype "bidirectional"))
    )
    (net (code "182") (name "unconnected-(U1-PC20-Pad131)") (class "Default")
      (node (ref "U1") (pin "131") (pinfunction "PC20_131") (pintype "bidirectional"))
    )
    (net (code "183") (name "unconnected-(U1-PC26-Pad137)") (class "Default")
      (node (ref "U1") (pin "137") (pinfunction "PC26_137") (pintype "bidirectional"))
    )
    (net (code "184") (name "unconnected-(U1-PC27-Pad138)") (class "Default")
      (node (ref "U1") (pin "138") (pinfunction "PC27_138") (pintype "bidirectional"))
    )
    (net (code "185") (name "unconnected-(U1-PC29-Pad102)") (class "Default")
      (node (ref "U1") (pin "102") (pinfunction "PC29_102") (pintype "bidirectional"))
    )
    (net (code "186") (name "unconnected-(U1-SHDN-Pad50)") (class "Default")
      (node (ref "U1") (pin "50") (pinfunction "SHDN_50") (pintype "output"))
    )
    (net (code "187") (name "unconnected-(U2-ST-Pad4)") (class "Default")
      (node (ref "U2") (pin "4") (pinfunction "ST_4") (pintype "bidirectional"))
    )
  )
)
